# PortExpanderCP2130.net
KiCad netlist of a schematic drawn in EAGLE
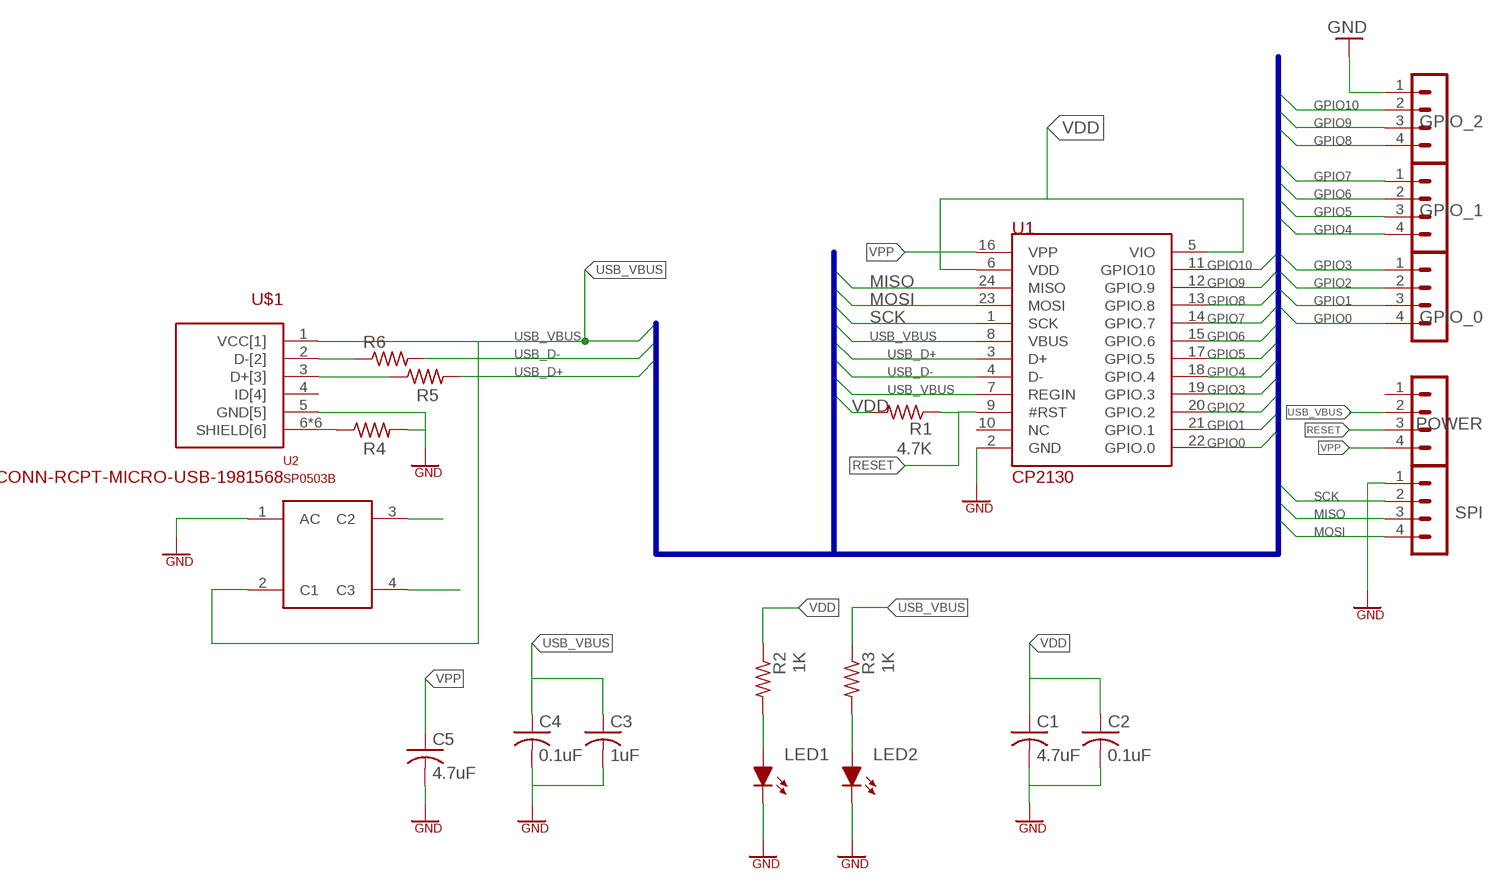
[diagram p0: schematic, sheet 1]

(export (version "E")
  (design (tool "Eeschema 10.0.6"))
  (components
    (comp (ref "C1")
      (value "4.7uF")
      (footprint "eagle-import:C1206")
      (libsource (lib "eagle-import") (part "C-USC1206"))
    )
    (comp (ref "C2")
      (value "0.1uF")
      (footprint "eagle-import:C1206")
      (libsource (lib "eagle-import") (part "C-USC1206"))
    )
    (comp (ref "C3")
      (value "1uF")
      (footprint "eagle-import:C1206")
      (libsource (lib "eagle-import") (part "C-USC1206"))
    )
    (comp (ref "C4")
      (value "0.1uF")
      (footprint "eagle-import:C1206")
      (libsource (lib "eagle-import") (part "C-USC1206"))
    )
    (comp (ref "C5")
      (value "4.7uF")
      (footprint "eagle-import:C1206")
      (libsource (lib "eagle-import") (part "C-USC1206"))
    )
    (comp (ref "GPIO_0")
      (value "MA04-1")
      (footprint "eagle-import:MA04-1")
      (libsource (lib "eagle-import") (part "MA04-1"))
    )
    (comp (ref "GPIO_1")
      (value "MA04-1")
      (footprint "eagle-import:MA04-1")
      (libsource (lib "eagle-import") (part "MA04-1"))
    )
    (comp (ref "GPIO_2")
      (value "MA04-1")
      (footprint "eagle-import:MA04-1")
      (libsource (lib "eagle-import") (part "MA04-1"))
    )
    (comp (ref "LED1")
      (value "LED_0805")
      (footprint "eagle-import:LED_0805")
      (libsource (lib "eagle-import") (part "LED_0805"))
    )
    (comp (ref "LED2")
      (value "LED_0805")
      (footprint "eagle-import:LED_0805")
      (libsource (lib "eagle-import") (part "LED_0805"))
    )
    (comp (ref "POWER")
      (value "MA04-1")
      (footprint "eagle-import:MA04-1")
      (libsource (lib "eagle-import") (part "MA04-1"))
    )
    (comp (ref "R1")
      (value "4.7K")
      (footprint "eagle-import:R1206")
      (libsource (lib "eagle-import") (part "R-US_R1206"))
    )
    (comp (ref "R2")
      (value "1K")
      (footprint "eagle-import:R1206")
      (libsource (lib "eagle-import") (part "R-US_R1206"))
    )
    (comp (ref "R3")
      (value "1K")
      (footprint "eagle-import:R1206")
      (libsource (lib "eagle-import") (part "R-US_R1206"))
    )
    (comp (ref "R4")
      (value "R-US_R1206")
      (footprint "eagle-import:R1206")
      (libsource (lib "eagle-import") (part "R-US_R1206"))
    )
    (comp (ref "R5")
      (value "R-US_R1206")
      (footprint "eagle-import:R1206")
      (libsource (lib "eagle-import") (part "R-US_R1206"))
    )
    (comp (ref "R6")
      (value "R-US_R1206")
      (footprint "eagle-import:R1206")
      (libsource (lib "eagle-import") (part "R-US_R1206"))
    )
    (comp (ref "SPI")
      (value "MA04-1")
      (footprint "eagle-import:MA04-1")
      (libsource (lib "eagle-import") (part "MA04-1"))
    )
    (comp (ref "U$1")
      (value "CONN-RCPT-MICRO-USB-1981568")
      (footprint "eagle-import:MICRO-USB-RCPT-1981568")
      (libsource (lib "eagle-import") (part "CONN-RCPT-MICRO-USB-1981568"))
    )
    (comp (ref "U1")
      (value "CP2130")
      (footprint "eagle-import:QFN-24")
      (libsource (lib "eagle-import") (part "CP2130"))
    )
    (comp (ref "U2")
      (value "SP0503B")
      (footprint "eagle-import:SOT143")
      (libsource (lib "eagle-import") (part "SP0503BSOT143"))
    )
  )
  (nets
    (net (code "1") (name "/GPIO0") (class "Default")
      (node (ref "GPIO_0") (pin "4") (pinfunction "4_4") (pintype "passive"))
      (node (ref "U1") (pin "22") (pinfunction "GPIO.0_22") (pintype "bidirectional"))
    )
    (net (code "2") (name "/GPIO1") (class "Default")
      (node (ref "GPIO_0") (pin "3") (pinfunction "3_3") (pintype "passive"))
      (node (ref "U1") (pin "21") (pinfunction "GPIO.1_21") (pintype "bidirectional"))
    )
    (net (code "3") (name "/GPIO2") (class "Default")
      (node (ref "GPIO_0") (pin "2") (pinfunction "2_2") (pintype "passive"))
      (node (ref "U1") (pin "20") (pinfunction "GPIO.2_20") (pintype "bidirectional"))
    )
    (net (code "4") (name "/GPIO3") (class "Default")
      (node (ref "GPIO_0") (pin "1") (pinfunction "1_1") (pintype "passive"))
      (node (ref "U1") (pin "19") (pinfunction "GPIO.3_19") (pintype "bidirectional"))
    )
    (net (code "5") (name "/GPIO4") (class "Default")
      (node (ref "GPIO_1") (pin "4") (pinfunction "4_4") (pintype "passive"))
      (node (ref "U1") (pin "18") (pinfunction "GPIO.4_18") (pintype "bidirectional"))
    )
    (net (code "6") (name "/GPIO5") (class "Default")
      (node (ref "GPIO_1") (pin "3") (pinfunction "3_3") (pintype "passive"))
      (node (ref "U1") (pin "17") (pinfunction "GPIO.5_17") (pintype "bidirectional"))
    )
    (net (code "7") (name "/GPIO6") (class "Default")
      (node (ref "GPIO_1") (pin "2") (pinfunction "2_2") (pintype "passive"))
      (node (ref "U1") (pin "15") (pinfunction "GPIO.6_15") (pintype "bidirectional"))
    )
    (net (code "8") (name "/GPIO7") (class "Default")
      (node (ref "GPIO_1") (pin "1") (pinfunction "1_1") (pintype "passive"))
      (node (ref "U1") (pin "14") (pinfunction "GPIO.7_14") (pintype "bidirectional"))
    )
    (net (code "9") (name "/GPIO8") (class "Default")
      (node (ref "GPIO_2") (pin "4") (pinfunction "4_4") (pintype "passive"))
      (node (ref "U1") (pin "13") (pinfunction "GPIO.8_13") (pintype "bidirectional"))
    )
    (net (code "10") (name "/GPIO9") (class "Default")
      (node (ref "GPIO_2") (pin "3") (pinfunction "3_3") (pintype "passive"))
      (node (ref "U1") (pin "12") (pinfunction "GPIO.9_12") (pintype "bidirectional"))
    )
    (net (code "11") (name "/GPIO10") (class "Default")
      (node (ref "GPIO_2") (pin "2") (pinfunction "2_2") (pintype "passive"))
      (node (ref "U1") (pin "11") (pinfunction "GPIO10_11") (pintype "bidirectional"))
    )
    (net (code "12") (name "/MISO") (class "Default")
      (node (ref "SPI") (pin "3") (pinfunction "3_3") (pintype "passive"))
      (node (ref "U1") (pin "24") (pinfunction "MISO_24") (pintype "bidirectional"))
    )
    (net (code "13") (name "/MOSI") (class "Default")
      (node (ref "SPI") (pin "4") (pinfunction "4_4") (pintype "passive"))
      (node (ref "U1") (pin "23") (pinfunction "MOSI_23") (pintype "bidirectional"))
    )
    (net (code "14") (name "/SCK") (class "Default")
      (node (ref "SPI") (pin "2") (pinfunction "2_2") (pintype "passive"))
      (node (ref "U1") (pin "1") (pinfunction "SCK_1") (pintype "bidirectional"))
    )
    (net (code "15") (name "/USB_D+") (class "Default")
      (node (ref "R5") (pin "2") (pinfunction "2_2") (pintype "passive"))
      (node (ref "U1") (pin "3") (pinfunction "D+_3") (pintype "bidirectional"))
    )
    (net (code "16") (name "/USB_D-") (class "Default")
      (node (ref "R6") (pin "2") (pinfunction "2_2") (pintype "passive"))
      (node (ref "U1") (pin "4") (pinfunction "D-_4") (pintype "bidirectional"))
    )
    (net (code "17") (name "GND") (class "Default")
      (node (ref "C1") (pin "2") (pinfunction "2_2") (pintype "passive"))
      (node (ref "C2") (pin "2") (pinfunction "2_2") (pintype "passive"))
      (node (ref "C3") (pin "2") (pinfunction "2_2") (pintype "passive"))
      (node (ref "C4") (pin "2") (pinfunction "2_2") (pintype "passive"))
      (node (ref "C5") (pin "2") (pinfunction "2_2") (pintype "passive"))
      (node (ref "GPIO_2") (pin "1") (pinfunction "1_1") (pintype "passive"))
      (node (ref "LED1") (pin "C") (pinfunction "C_C") (pintype "passive"))
      (node (ref "LED2") (pin "C") (pinfunction "C_C") (pintype "passive"))
      (node (ref "R4") (pin "2") (pinfunction "2_2") (pintype "passive"))
      (node (ref "SPI") (pin "1") (pinfunction "1_1") (pintype "passive"))
      (node (ref "U$1") (pin "5") (pinfunction "GND[5]_5") (pintype "bidirectional"))
      (node (ref "U1") (pin "2") (pinfunction "GND_2") (pintype "bidirectional"))
      (node (ref "U2") (pin "1") (pinfunction "AC_1") (pintype "bidirectional"))
    )
    (net (code "18") (name "Net-(LED1-PadA)") (class "Default")
      (node (ref "LED1") (pin "A") (pinfunction "A_A") (pintype "passive"))
      (node (ref "R2") (pin "2") (pinfunction "2_2") (pintype "passive"))
    )
    (net (code "19") (name "Net-(LED2-PadA)") (class "Default")
      (node (ref "LED2") (pin "A") (pinfunction "A_A") (pintype "passive"))
      (node (ref "R3") (pin "2") (pinfunction "2_2") (pintype "passive"))
    )
    (net (code "20") (name "Net-(R4-Pad1)") (class "Default")
      (node (ref "R4") (pin "1") (pinfunction "1_1") (pintype "passive"))
      (node (ref "U$1") (pin "10") (pinfunction "SHIELD[6]_10") (pintype "bidirectional"))
      (node (ref "U$1") (pin "11") (pinfunction "SHIELD[6]_11") (pintype "bidirectional"))
      (node (ref "U$1") (pin "6") (pinfunction "SHIELD[6]_6") (pintype "bidirectional"))
      (node (ref "U$1") (pin "7") (pinfunction "SHIELD[6]_7") (pintype "bidirectional"))
      (node (ref "U$1") (pin "8") (pinfunction "SHIELD[6]_8") (pintype "bidirectional"))
      (node (ref "U$1") (pin "9") (pinfunction "SHIELD[6]_9") (pintype "bidirectional"))
    )
    (net (code "21") (name "Net-(U$1-D+[3])") (class "Default")
      (node (ref "R5") (pin "1") (pinfunction "1_1") (pintype "passive"))
      (node (ref "U$1") (pin "3") (pinfunction "D+[3]_3") (pintype "bidirectional"))
    )
    (net (code "22") (name "Net-(U$1-D-[2])") (class "Default")
      (node (ref "R6") (pin "1") (pinfunction "1_1") (pintype "passive"))
      (node (ref "U$1") (pin "2") (pinfunction "D-[2]_2") (pintype "bidirectional"))
    )
    (net (code "23") (name "RESET") (class "Default")
      (node (ref "POWER") (pin "3") (pinfunction "3_3") (pintype "passive"))
      (node (ref "R1") (pin "1") (pinfunction "1_1") (pintype "passive"))
      (node (ref "U1") (pin "9") (pinfunction "#RST_9") (pintype "bidirectional"))
    )
    (net (code "24") (name "USB_VBUS") (class "Default")
      (node (ref "C3") (pin "1") (pinfunction "1_1") (pintype "passive"))
      (node (ref "C4") (pin "1") (pinfunction "1_1") (pintype "passive"))
      (node (ref "POWER") (pin "2") (pinfunction "2_2") (pintype "passive"))
      (node (ref "R3") (pin "1") (pinfunction "1_1") (pintype "passive"))
      (node (ref "U$1") (pin "1") (pinfunction "VCC[1]_1") (pintype "bidirectional"))
      (node (ref "U1") (pin "7") (pinfunction "REGIN_7") (pintype "bidirectional"))
      (node (ref "U1") (pin "8") (pinfunction "VBUS_8") (pintype "bidirectional"))
      (node (ref "U2") (pin "2") (pinfunction "C1_2") (pintype "bidirectional"))
    )
    (net (code "25") (name "VDD") (class "Default")
      (node (ref "C1") (pin "1") (pinfunction "1_1") (pintype "passive"))
      (node (ref "C2") (pin "1") (pinfunction "1_1") (pintype "passive"))
      (node (ref "R1") (pin "2") (pinfunction "2_2") (pintype "passive"))
      (node (ref "R2") (pin "1") (pinfunction "1_1") (pintype "passive"))
      (node (ref "U1") (pin "5") (pinfunction "VIO_5") (pintype "bidirectional"))
      (node (ref "U1") (pin "6") (pinfunction "VDD_6") (pintype "bidirectional"))
    )
    (net (code "26") (name "VPP") (class "Default")
      (node (ref "C5") (pin "1") (pinfunction "1_1") (pintype "passive"))
      (node (ref "POWER") (pin "4") (pinfunction "4_4") (pintype "passive"))
      (node (ref "U1") (pin "16") (pinfunction "VPP_16") (pintype "bidirectional"))
    )
    (net (code "27") (name "unconnected-(POWER-Pad1)") (class "Default")
      (node (ref "POWER") (pin "1") (pinfunction "1_1") (pintype "passive"))
    )
    (net (code "28") (name "unconnected-(U$1-ID[4]-Pad4)") (class "Default")
      (node (ref "U$1") (pin "4") (pinfunction "ID[4]_4") (pintype "bidirectional"))
    )
    (net (code "29") (name "unconnected-(U1-NC-Pad10)") (class "Default")
      (node (ref "U1") (pin "10") (pinfunction "NC_10") (pintype "bidirectional"))
    )
    (net (code "30") (name "unconnected-(U2-C2-Pad3)") (class "Default")
      (node (ref "U2") (pin "3") (pinfunction "C2_3") (pintype "bidirectional"))
    )
    (net (code "31") (name "unconnected-(U2-C3-Pad4)") (class "Default")
      (node (ref "U2") (pin "4") (pinfunction "C3_4") (pintype "bidirectional"))
    )
  )
)
